# 6_battery_heater_controller.net
KiCad netlist of a schematic drawn in Altium Designer
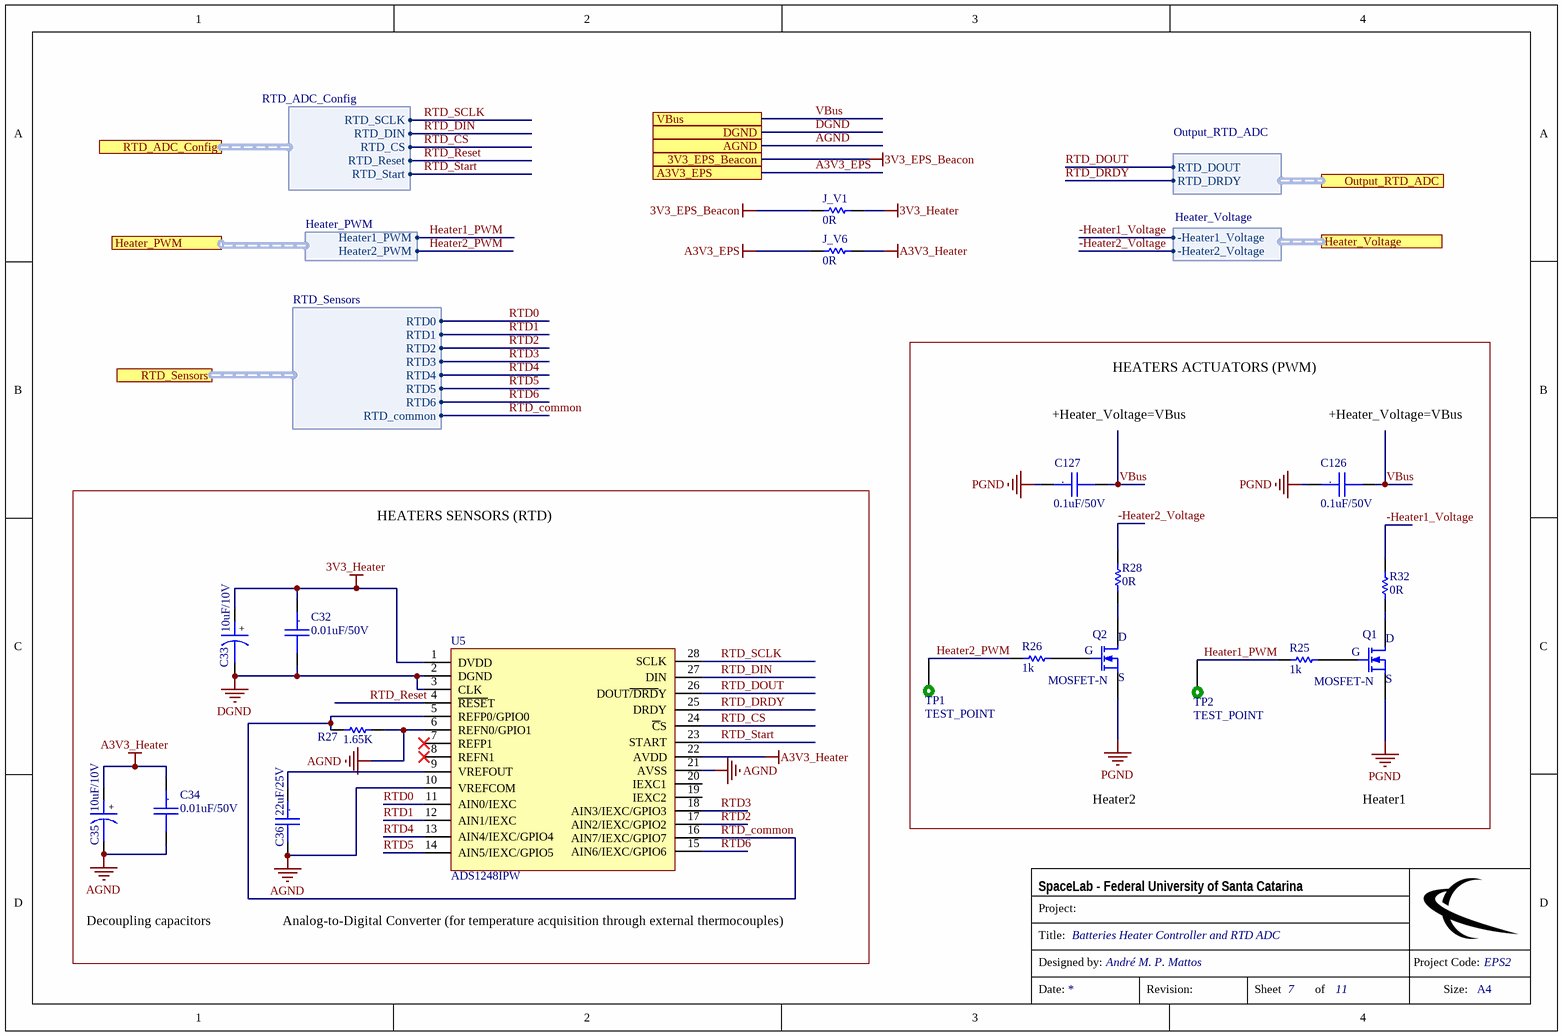
[diagram p0: 6_battery_heater_controller.schdoc]

(export (version "E")
  (design (tool "Eeschema 10.0.6"))
  (components
    (comp (ref "C32")
      (value "0.01uF/50V")
      (footprint "CC0805")
      (description "CAP CER 0.01uF 50V 10% X7R 0805")
      (fields (field (name "PARTNUMBER") "08055C103KAT4A") (field (name "MANUFACTURER") "Kyocera AVX"))
      (libsource (lib "PCB_Project_FlightModel_EPS") (part "Cap_Cer_X7R_0.01uF_50V_0805"))
    )
    (comp (ref "C33")
      (value "10uF/10V")
      (footprint "FloripaSatPcbLib:CC0805_Tantalum")
      (description "CAP Tantalum 10uF 6.3V 10% 0805")
      (fields (field (name "PARTNUMBER") "TPSR106K006R1000") (field (name "MANUFACTURER") "Kyocera AVX"))
      (libsource (lib "PCB_Project_FlightModel_EPS") (part "Cap_Tant_SMD_10uF_6V3_0805"))
    )
    (comp (ref "C34")
      (value "0.01uF/50V")
      (footprint "CC0805")
      (description "CAP CER 0.01uF 50V 10% X7R 0805")
      (fields (field (name "PARTNUMBER") "08055C103KAT4A") (field (name "MANUFACTURER") "Kyocera AVX"))
      (libsource (lib "PCB_Project_FlightModel_EPS") (part "Cap_Cer_X7R_0.01uF_50V_0805"))
    )
    (comp (ref "C35")
      (value "10uF/10V")
      (footprint "FloripaSatPcbLib:CC0805_Tantalum")
      (description "CAP Tantalum 10uF 6.3V 10% 0805")
      (fields (field (name "PARTNUMBER") "TPSR106K006R1000") (field (name "MANUFACTURER") "Kyocera AVX"))
      (libsource (lib "PCB_Project_FlightModel_EPS") (part "Cap_Tant_SMD_10uF_6V3_0805"))
    )
    (comp (ref "C36")
      (value "22uF/25V")
      (footprint "CC1210")
      (description "CAP CER 22uF 25V 10% X7R 1210")
      (fields (field (name "PARTNUMBER") "GRM32ER71E226KE15L") (field (name "MANUFACTURER") "Murata"))
      (libsource (lib "PCB_Project_FlightModel_EPS") (part "Cap_Cer_X7R_22uF_25V_1210"))
    )
    (comp (ref "C126")
      (value "0.1uF/50V")
      (footprint "CC0805")
      (description "CAP CER 0.1UF 50V 10% X7R 0805")
      (fields (field (name "PARTNUMBER") "CC0805KRX7R9BB104") (field (name "MANUFACTURER") "Yageo"))
      (libsource (lib "PCB_Project_FlightModel_EPS") (part "Cap_Cer_X7R_0.1uF_50V_0805"))
    )
    (comp (ref "C127")
      (value "0.1uF/50V")
      (footprint "CC0805")
      (description "CAP CER 0.1UF 50V 10% X7R 0805")
      (fields (field (name "PARTNUMBER") "CC0805KRX7R9BB104") (field (name "MANUFACTURER") "Yageo"))
      (libsource (lib "PCB_Project_FlightModel_EPS") (part "Cap_Cer_X7R_0.1uF_50V_0805"))
    )
    (comp (ref "J_V1")
      (value "0R")
      (footprint "0805")
      (description "RES 0R OHM 1/8W JUMPER 0805")
      (fields (field (name "PARTNUMBER") "CRCW08050000Z0EA") (field (name "MANUFACTURER") "Vishay"))
      (libsource (lib "PCB_Project_FlightModel_EPS") (part "R0R_JUMPER_1/8W_0805"))
    )
    (comp (ref "J_V6")
      (value "0R")
      (footprint "0805")
      (description "RES 0R OHM 1/8W JUMPER 0805")
      (fields (field (name "PARTNUMBER") "CRCW08050000Z0EA") (field (name "MANUFACTURER") "Vishay"))
      (libsource (lib "PCB_Project_FlightModel_EPS") (part "R0R_JUMPER_1/8W_0805"))
    )
    (comp (ref "Q1")
      (value "MOSFET-N")
      (footprint "SOIC8_Mosfet")
      (description "MOSFET N-Channel 30V Vds 20V Vgs SO-8")
      (fields
        (field (name "PARTNUMBER") "SI4166DY-T1-GE3")
        (field (name "MANUFACTURER") "Vishay Siliconix")
        (field (name "PUBLISHER") "Altium Limited")
      )
      (libsource (lib "PCB_Project_FlightModel_EPS") (part "MOSFET-N_30V_SI4166DY"))
    )
    (comp (ref "Q2")
      (value "MOSFET-N")
      (footprint "SOIC8_Mosfet")
      (description "MOSFET N-Channel 30V Vds 20V Vgs SO-8")
      (fields
        (field (name "PARTNUMBER") "SI4166DY-T1-GE3")
        (field (name "MANUFACTURER") "Vishay Siliconix")
        (field (name "PUBLISHER") "Altium Limited")
      )
      (libsource (lib "PCB_Project_FlightModel_EPS") (part "MOSFET-N_30V_SI4166DY"))
    )
    (comp (ref "R25")
      (value "1k")
      (footprint "0805")
      (description "RES SMD 1K OHM 1% 1/8W 0805")
      (fields (field (name "MANUFACTURER") "Panasonic") (field (name "TOLERANCE") "1%"))
      (libsource (lib "PCB_Project_FlightModel_EPS") (part "R1.0k_1%_1/8W_0805"))
    )
    (comp (ref "R26")
      (value "1k")
      (footprint "0805")
      (description "RES SMD 1K OHM 1% 1/8W 0805")
      (fields (field (name "MANUFACTURER") "Panasonic") (field (name "TOLERANCE") "1%"))
      (libsource (lib "PCB_Project_FlightModel_EPS") (part "R1.0k_1%_1/8W_0805"))
    )
    (comp (ref "R27")
      (value "1.65K")
      (footprint "0805")
      (description "RES 1.65K OHM 1/10W 0.1% 0805")
      (fields (field (name "PARTNUMBER") "PCF0805R-1K65BT1") (field (name "MANUFACTURER") "TT Welwyn"))
      (libsource (lib "PCB_Project_FlightModel_EPS") (part "R1.65K_1%_1/10W_0805"))
    )
    (comp (ref "R28")
      (value "0R")
      (footprint "0805")
      (description "RES 0R OHM 1/8W JUMPER 0805")
      (fields (field (name "PARTNUMBER") "CRCW08050000Z0EA") (field (name "MANUFACTURER") "Vishay"))
      (libsource (lib "PCB_Project_FlightModel_EPS") (part "R0R_JUMPER_1/8W_0805"))
    )
    (comp (ref "R32")
      (value "0R")
      (footprint "0805")
      (description "RES 0R OHM 1/8W JUMPER 0805")
      (fields (field (name "PARTNUMBER") "CRCW08050000Z0EA") (field (name "MANUFACTURER") "Vishay"))
      (libsource (lib "PCB_Project_FlightModel_EPS") (part "R0R_JUMPER_1/8W_0805"))
    )
    (comp (ref "TP1")
      (value "TEST_POINT")
      (footprint "TEST_POINT")
      (description "Test point")
      (libsource (lib "PCB_Project_FlightModel_EPS") (part "TEST_POINT"))
    )
    (comp (ref "TP2")
      (value "TEST_POINT")
      (footprint "TEST_POINT")
      (description "Test point")
      (libsource (lib "PCB_Project_FlightModel_EPS") (part "TEST_POINT"))
    )
    (comp (ref "U5")
      (value "ADS1248IPW")
      (footprint "TSSOP28")
      (description "24 bit ADC Differential Input, SPI, 28-pin TSSOP")
      (fields (field (name "MANUFACTURER") "Texas Instruments") (field (name "PART_NUMBER") "ADS1248IPWR"))
      (libsource (lib "PCB_Project_FlightModel_EPS") (part "ADS1248IPW"))
    )
  )
  (nets
    (net (code "6") (name "/-Heater1_Voltage") (class "Default")
      (node (ref "R32") (pin "1") (pinfunction "1_1") (pintype "passive"))
    )
    (net (code "7") (name "/-Heater2_Voltage") (class "Default")
      (node (ref "R28") (pin "1") (pinfunction "1_1") (pintype "passive"))
    )
    (net (code "8") (name "/Heater1_PWM") (class "Default")
      (node (ref "R25") (pin "2") (pinfunction "2_2") (pintype "passive"))
      (node (ref "TP2") (pin "1") (pinfunction "1_1") (pintype "passive"))
    )
    (net (code "9") (name "/Heater2_PWM") (class "Default")
      (node (ref "R26") (pin "2") (pinfunction "2_2") (pintype "passive"))
      (node (ref "TP1") (pin "1") (pinfunction "1_1") (pintype "passive"))
    )
    (net (code "10") (name "/RTD0") (class "Default")
      (node (ref "U5") (pin "11") (pinfunction "AIN0/IEXC_11") (pintype "passive"))
    )
    (net (code "11") (name "/RTD1") (class "Default")
      (node (ref "U5") (pin "12") (pinfunction "AIN1/IEXC_12") (pintype "passive"))
    )
    (net (code "12") (name "/RTD2") (class "Default")
      (node (ref "U5") (pin "17") (pinfunction "AIN2/IEXC/GPIO2_17") (pintype "passive"))
    )
    (net (code "13") (name "/RTD3") (class "Default")
      (node (ref "U5") (pin "18") (pinfunction "AIN3/IEXC/GPIO3_18") (pintype "passive"))
    )
    (net (code "14") (name "/RTD4") (class "Default")
      (node (ref "U5") (pin "13") (pinfunction "AIN4/IEXC/GPIO4_13") (pintype "passive"))
    )
    (net (code "15") (name "/RTD5") (class "Default")
      (node (ref "U5") (pin "14") (pinfunction "AIN5/IEXC/GPIO5_14") (pintype "passive"))
    )
    (net (code "16") (name "/RTD6") (class "Default")
      (node (ref "U5") (pin "15") (pinfunction "AIN6/IEXC/GPIO6_15") (pintype "power_in"))
    )
    (net (code "17") (name "/RTD_CS") (class "Default")
      (node (ref "U5") (pin "24") (pinfunction "~{C}S_24") (pintype "passive"))
    )
    (net (code "18") (name "/RTD_DIN") (class "Default")
      (node (ref "U5") (pin "27") (pinfunction "DIN_27") (pintype "passive"))
    )
    (net (code "19") (name "/RTD_DOUT") (class "Default")
      (node (ref "U5") (pin "26") (pinfunction "DOUT~{/DRD}Y_26") (pintype "passive"))
    )
    (net (code "20") (name "/RTD_DRDY") (class "Default")
      (node (ref "U5") (pin "25") (pinfunction "DRDY_25") (pintype "passive"))
    )
    (net (code "21") (name "/RTD_Reset") (class "Default")
      (node (ref "U5") (pin "4") (pinfunction "~{RESE}T_4") (pintype "passive"))
    )
    (net (code "22") (name "/RTD_SCLK") (class "Default")
      (node (ref "U5") (pin "28") (pinfunction "SCLK_28") (pintype "passive"))
    )
    (net (code "23") (name "/RTD_Start") (class "Default")
      (node (ref "U5") (pin "23") (pinfunction "START_23") (pintype "passive"))
    )
    (net (code "24") (name "/RTD_common") (class "Default")
      (node (ref "R27") (pin "2") (pinfunction "2_2") (pintype "passive"))
      (node (ref "U5") (pin "16") (pinfunction "AIN7/IEXC/GPIO7_16") (pintype "power_in"))
      (node (ref "U5") (pin "5") (pinfunction "REFP0/GPIO0_5") (pintype "passive"))
    )
    (net (code "25") (name "/VBus") (class "Default")
      (node (ref "C126") (pin "2") (pinfunction "2_2") (pintype "passive"))
      (node (ref "C127") (pin "2") (pinfunction "2_2") (pintype "passive"))
    )
    (net (code "31") (name "3V3_EPS_Beacon") (class "Default")
      (node (ref "J_V1") (pin "2") (pinfunction "2_2") (pintype "passive"))
    )
    (net (code "32") (name "3V3_Heater") (class "Default")
      (node (ref "C32") (pin "1") (pinfunction "1_1") (pintype "passive"))
      (node (ref "C33") (pin "1") (pinfunction "1_1") (pintype "passive"))
      (node (ref "J_V1") (pin "1") (pinfunction "1_1") (pintype "passive"))
      (node (ref "U5") (pin "1") (pinfunction "DVDD_1") (pintype "power_in"))
    )
    (net (code "33") (name "A3V3_EPS") (class "Default")
      (node (ref "J_V6") (pin "2") (pinfunction "2_2") (pintype "passive"))
    )
    (net (code "34") (name "A3V3_Heater") (class "Default")
      (node (ref "C34") (pin "1") (pinfunction "1_1") (pintype "passive"))
      (node (ref "C35") (pin "1") (pinfunction "1_1") (pintype "passive"))
      (node (ref "J_V6") (pin "1") (pinfunction "1_1") (pintype "passive"))
      (node (ref "U5") (pin "22") (pinfunction "AVDD_22") (pintype "passive"))
    )
    (net (code "35") (name "AGND") (class "Default")
      (node (ref "C34") (pin "2") (pinfunction "2_2") (pintype "passive"))
      (node (ref "C35") (pin "2") (pinfunction "2_2") (pintype "passive"))
      (node (ref "C36") (pin "2") (pinfunction "2_2") (pintype "passive"))
      (node (ref "R27") (pin "1") (pinfunction "1_1") (pintype "passive"))
      (node (ref "U5") (pin "10") (pinfunction "VREFCOM_10") (pintype "passive"))
      (node (ref "U5") (pin "21") (pinfunction "AVSS_21") (pintype "passive"))
      (node (ref "U5") (pin "6") (pinfunction "REFN0/GPIO1_6") (pintype "passive"))
    )
    (net (code "36") (name "DGND") (class "Default")
      (node (ref "C32") (pin "2") (pinfunction "2_2") (pintype "passive"))
      (node (ref "C33") (pin "2") (pinfunction "2_2") (pintype "passive"))
      (node (ref "U5") (pin "2") (pinfunction "DGND_2") (pintype "power_in"))
      (node (ref "U5") (pin "3") (pinfunction "CLK_3") (pintype "passive"))
    )
    (net (code "37") (name "Net-(Q1-D)") (class "Default")
      (node (ref "Q1") (pin "3") (pinfunction "D_3") (pintype "passive"))
      (node (ref "R32") (pin "2") (pinfunction "2_2") (pintype "passive"))
    )
    (net (code "38") (name "Net-(Q1-G)") (class "Default")
      (node (ref "Q1") (pin "2") (pinfunction "G_2") (pintype "passive"))
      (node (ref "R25") (pin "1") (pinfunction "1_1") (pintype "passive"))
    )
    (net (code "39") (name "Net-(Q2-D)") (class "Default")
      (node (ref "Q2") (pin "3") (pinfunction "D_3") (pintype "passive"))
      (node (ref "R28") (pin "2") (pinfunction "2_2") (pintype "passive"))
    )
    (net (code "40") (name "Net-(Q2-G)") (class "Default")
      (node (ref "Q2") (pin "2") (pinfunction "G_2") (pintype "passive"))
      (node (ref "R26") (pin "1") (pinfunction "1_1") (pintype "passive"))
    )
    (net (code "41") (name "Net-(U5-VREFOUT)") (class "Default")
      (node (ref "C36") (pin "1") (pinfunction "1_1") (pintype "passive"))
      (node (ref "U5") (pin "9") (pinfunction "VREFOUT_9") (pintype "passive"))
    )
    (net (code "42") (name "PGND") (class "Default")
      (node (ref "C126") (pin "1") (pinfunction "1_1") (pintype "passive"))
      (node (ref "C127") (pin "1") (pinfunction "1_1") (pintype "passive"))
      (node (ref "Q1") (pin "1") (pinfunction "S_1") (pintype "passive"))
      (node (ref "Q2") (pin "1") (pinfunction "S_1") (pintype "passive"))
    )
    (net (code "43") (name "unconnected-(U5-IEXC1-Pad20)") (class "Default")
      (node (ref "U5") (pin "20") (pinfunction "IEXC1_20") (pintype "passive"))
    )
    (net (code "44") (name "unconnected-(U5-IEXC2-Pad19)") (class "Default")
      (node (ref "U5") (pin "19") (pinfunction "IEXC2_19") (pintype "passive"))
    )
    (net (code "45") (name "unconnected-(U5-REFN1-Pad8)") (class "Default")
      (node (ref "U5") (pin "8") (pinfunction "REFN1_8") (pintype "passive+no_connect"))
    )
    (net (code "46") (name "unconnected-(U5-REFP1-Pad7)") (class "Default")
      (node (ref "U5") (pin "7") (pinfunction "REFP1_7") (pintype "passive+no_connect"))
    )
  )
)
